# LCMeter_test_power_inverter_VER2.net
KiCad netlist of a schematic drawn in EAGLE
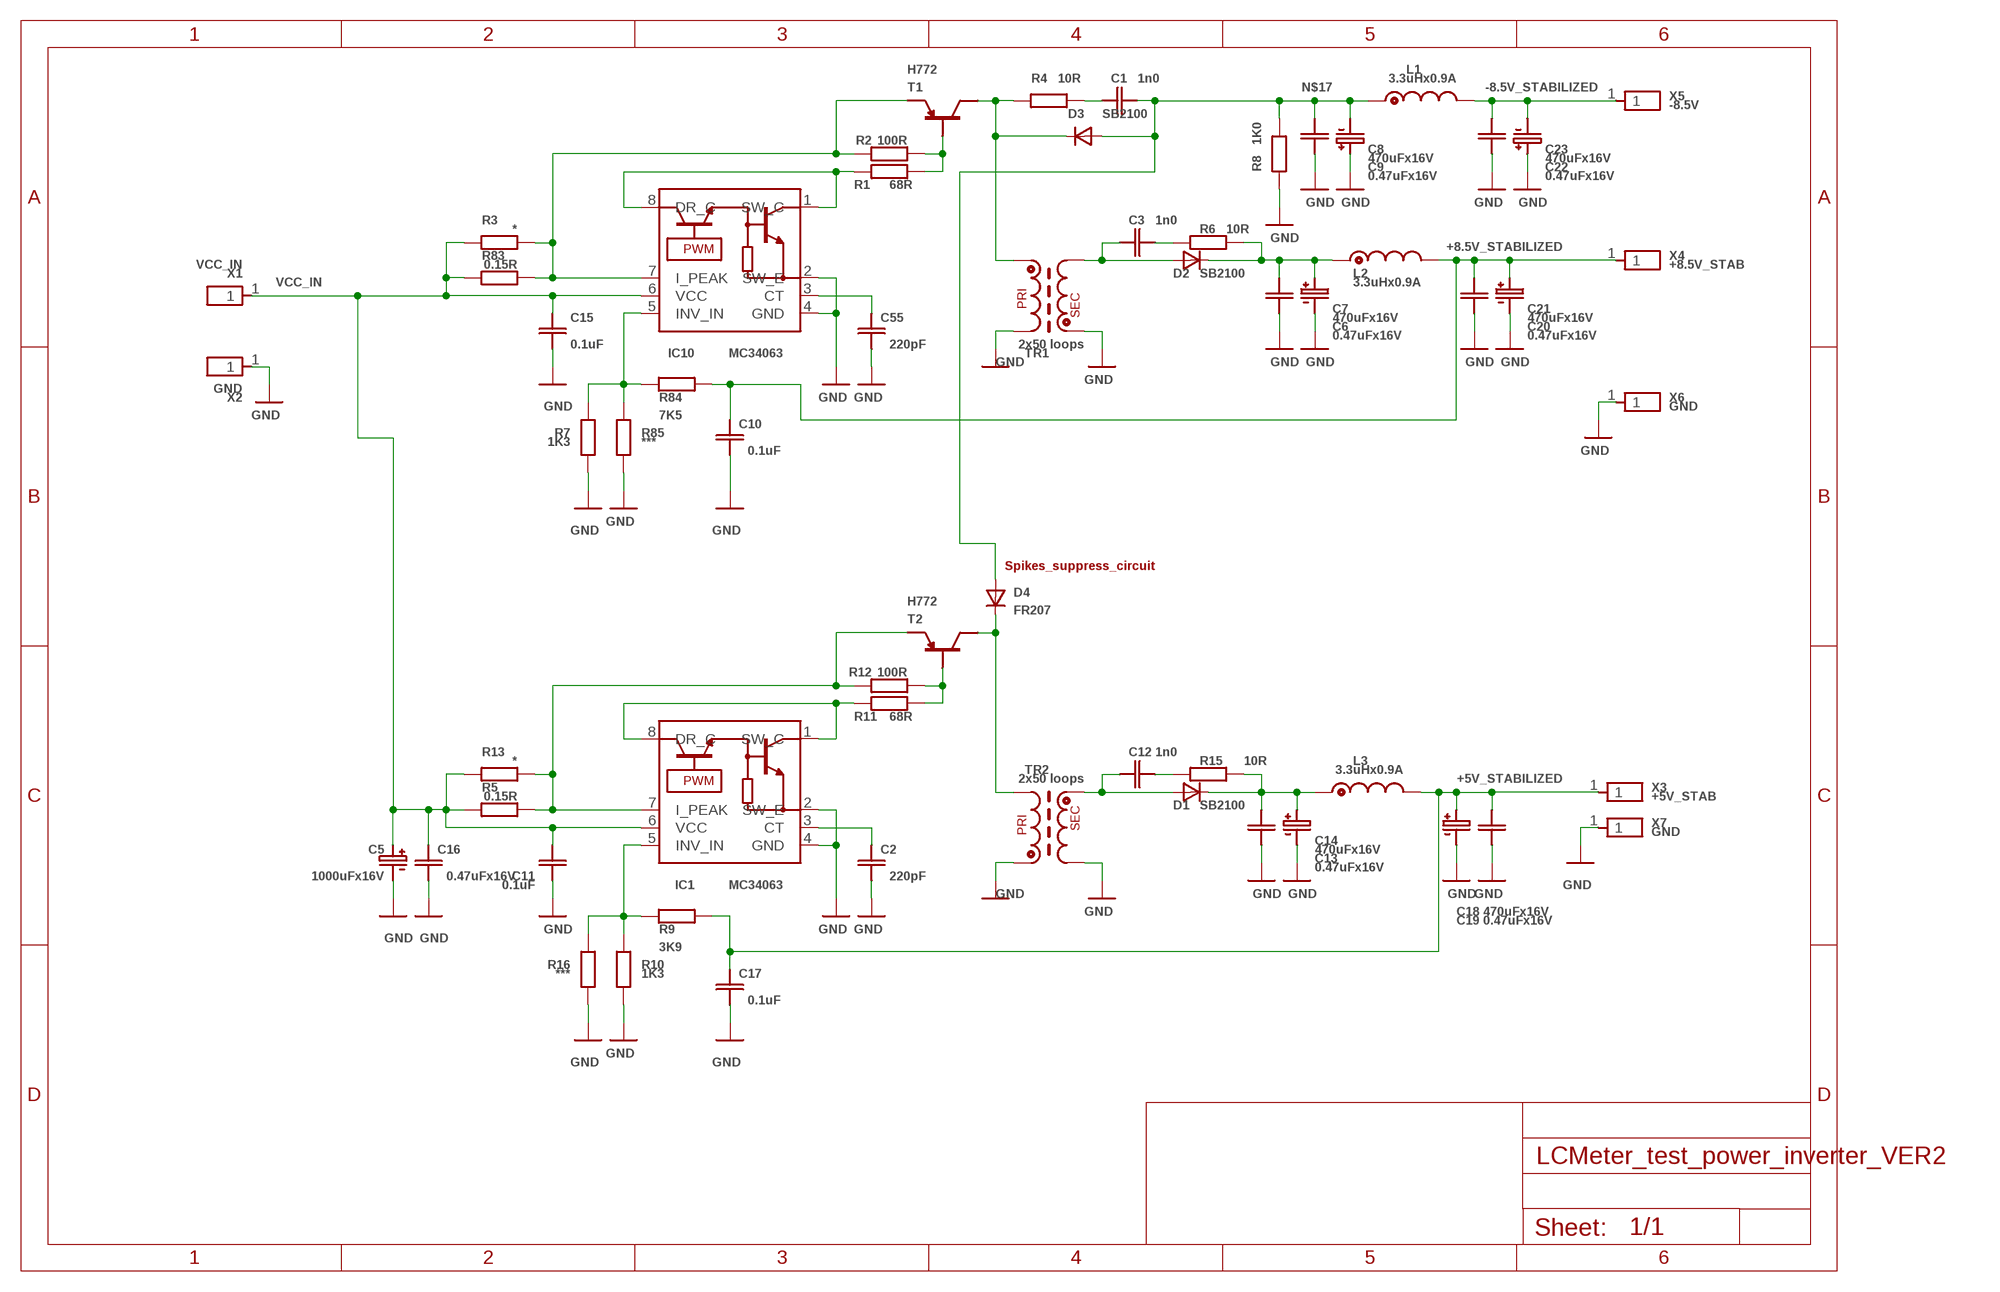
[diagram p0: schematic, sheet 1]

(export (version "E")
  (design (tool "Eeschema 10.0.6"))
  (components
    (comp (ref "C1")
      (value "1n0")
      (footprint "eagle-import:RSMD_0805")
      (libsource (lib "eagle-import") (part "CSMD_0805"))
    )
    (comp (ref "C2")
      (value "220pF")
      (footprint "eagle-import:RSMD_0805")
      (libsource (lib "eagle-import") (part "CSMD_0805"))
    )
    (comp (ref "C3")
      (value "1n0")
      (footprint "eagle-import:RSMD_0805")
      (libsource (lib "eagle-import") (part "CSMD_0805"))
    )
    (comp (ref "C5")
      (value "1000uFx16V")
      (footprint "eagle-import:CE_10MM")
      (libsource (lib "eagle-import") (part "CE10MM"))
    )
    (comp (ref "C6")
      (value "0.47uFx16V")
      (footprint "eagle-import:RSMD_1206_BIG_GAP")
      (libsource (lib "eagle-import") (part "CSMD_1206_BIG_GAP"))
    )
    (comp (ref "C7")
      (value "470uFx16V")
      (footprint "eagle-import:CE_10MM")
      (libsource (lib "eagle-import") (part "CE10MM"))
    )
    (comp (ref "C8")
      (value "470uFx16V")
      (footprint "eagle-import:CE_10MM")
      (libsource (lib "eagle-import") (part "CE10MM"))
    )
    (comp (ref "C9")
      (value "0.47uFx16V")
      (footprint "eagle-import:RSMD_1206_BIG_GAP")
      (libsource (lib "eagle-import") (part "CSMD_1206_BIG_GAP"))
    )
    (comp (ref "C10")
      (value "0.1uF")
      (footprint "eagle-import:RSMD_0805")
      (libsource (lib "eagle-import") (part "CSMD_0805"))
    )
    (comp (ref "C11")
      (value "0.1uF")
      (footprint "eagle-import:RSMD_0805")
      (libsource (lib "eagle-import") (part "CSMD_0805"))
    )
    (comp (ref "C12")
      (value "1n0")
      (footprint "eagle-import:RSMD_0805")
      (libsource (lib "eagle-import") (part "CSMD_0805"))
    )
    (comp (ref "C13")
      (value "0.47uFx16V")
      (footprint "eagle-import:RSMD_1206_BIG_GAP")
      (libsource (lib "eagle-import") (part "CSMD_1206_BIG_GAP"))
    )
    (comp (ref "C14")
      (value "470uFx16V")
      (footprint "eagle-import:CE_10MM")
      (libsource (lib "eagle-import") (part "CE10MM"))
    )
    (comp (ref "C15")
      (value "0.1uF")
      (footprint "eagle-import:RSMD_0805")
      (libsource (lib "eagle-import") (part "CSMD_0805"))
    )
    (comp (ref "C16")
      (value "0.47uFx16V")
      (footprint "eagle-import:RSMD_1206")
      (libsource (lib "eagle-import") (part "CSMD_1206"))
    )
    (comp (ref "C17")
      (value "0.1uF")
      (footprint "eagle-import:RSMD_0805")
      (libsource (lib "eagle-import") (part "CSMD_0805"))
    )
    (comp (ref "C18")
      (value "470uFx16V")
      (footprint "eagle-import:CE_10MM")
      (libsource (lib "eagle-import") (part "CE10MM"))
    )
    (comp (ref "C19")
      (value "0.47uFx16V")
      (footprint "eagle-import:RSMD_1206_BIG_GAP")
      (libsource (lib "eagle-import") (part "CSMD_1206_BIG_GAP"))
    )
    (comp (ref "C20")
      (value "0.47uFx16V")
      (footprint "eagle-import:RSMD_1206_BIG_GAP")
      (libsource (lib "eagle-import") (part "CSMD_1206_BIG_GAP"))
    )
    (comp (ref "C21")
      (value "470uFx16V")
      (footprint "eagle-import:CE_10MM")
      (libsource (lib "eagle-import") (part "CE10MM"))
    )
    (comp (ref "C22")
      (value "0.47uFx16V")
      (footprint "eagle-import:RSMD_1206_BIG_GAP")
      (libsource (lib "eagle-import") (part "CSMD_1206_BIG_GAP"))
    )
    (comp (ref "C23")
      (value "470uFx16V")
      (footprint "eagle-import:CE_10MM")
      (libsource (lib "eagle-import") (part "CE10MM"))
    )
    (comp (ref "C55")
      (value "220pF")
      (footprint "eagle-import:RSMD_0805")
      (libsource (lib "eagle-import") (part "CSMD_0805"))
    )
    (comp (ref "D1")
      (value "SB2100")
      (footprint "eagle-import:DO-41_5MM")
      (libsource (lib "eagle-import") (part "1N4001DO-41_5MM"))
    )
    (comp (ref "D2")
      (value "SB2100")
      (footprint "eagle-import:DO-41_5MM")
      (libsource (lib "eagle-import") (part "1N4001DO-41_5MM"))
    )
    (comp (ref "D3")
      (value "SB2100")
      (footprint "eagle-import:DO-41_5MM")
      (libsource (lib "eagle-import") (part "1N4001DO-41_5MM"))
    )
    (comp (ref "D4")
      (value "FR207")
      (footprint "eagle-import:DO-41_20MM")
      (libsource (lib "eagle-import") (part "1N4001DO-41_20MM"))
    )
    (comp (ref "IC1")
      (value "MC34063")
      (footprint "eagle-import:DIP8")
      (libsource (lib "eagle-import") (part "MC34063(DIP8)"))
    )
    (comp (ref "IC10")
      (value "MC34063")
      (footprint "eagle-import:DIP8")
      (libsource (lib "eagle-import") (part "MC34063(DIP8)"))
    )
    (comp (ref "L1")
      (value "3.3uHx0.9A")
      (footprint "eagle-import:L_SENIA")
      (libsource (lib "eagle-import") (part "L(SENIA)"))
    )
    (comp (ref "L2")
      (value "3.3uHx0.9A")
      (footprint "eagle-import:L_SENIA")
      (libsource (lib "eagle-import") (part "L(SENIA)"))
    )
    (comp (ref "L3")
      (value "3.3uHx0.9A")
      (footprint "eagle-import:L_SENIA")
      (libsource (lib "eagle-import") (part "L(SENIA)"))
    )
    (comp (ref "R1")
      (value "68R")
      (footprint "eagle-import:RSMD_0805")
      (libsource (lib "eagle-import") (part "RSMD_0805"))
    )
    (comp (ref "R2")
      (value "100R")
      (footprint "eagle-import:RSMD_0805")
      (libsource (lib "eagle-import") (part "RSMD_0805"))
    )
    (comp (ref "R3")
      (value "*")
      (footprint "eagle-import:RSMD_1206_BIG_GAP")
      (libsource (lib "eagle-import") (part "RSMD_1206_BIG_GAP"))
    )
    (comp (ref "R4")
      (value "10R")
      (footprint "eagle-import:RSMD_0805")
      (libsource (lib "eagle-import") (part "RSMD_0805"))
    )
    (comp (ref "R5")
      (value "0.15R")
      (footprint "eagle-import:RSMD_1206_BIG_GAP")
      (libsource (lib "eagle-import") (part "RSMD_1206_BIG_GAP"))
    )
    (comp (ref "R6")
      (value "10R")
      (footprint "eagle-import:RSMD_0805")
      (libsource (lib "eagle-import") (part "RSMD_0805"))
    )
    (comp (ref "R7")
      (value "1K3")
      (footprint "eagle-import:RSMD_0805")
      (libsource (lib "eagle-import") (part "RSMD_0805"))
    )
    (comp (ref "R8")
      (value "1K0")
      (footprint "eagle-import:RSMD_1206_BIG_GAP")
      (libsource (lib "eagle-import") (part "RSMD_1206_BIG_GAP"))
    )
    (comp (ref "R9")
      (value "3K9")
      (footprint "eagle-import:RSMD_0805")
      (libsource (lib "eagle-import") (part "RSMD_0805"))
    )
    (comp (ref "R10")
      (value "1K3")
      (footprint "eagle-import:RSMD_0805")
      (libsource (lib "eagle-import") (part "RSMD_0805"))
    )
    (comp (ref "R11")
      (value "68R")
      (footprint "eagle-import:RSMD_0805")
      (libsource (lib "eagle-import") (part "RSMD_0805"))
    )
    (comp (ref "R12")
      (value "100R")
      (footprint "eagle-import:RSMD_0805")
      (libsource (lib "eagle-import") (part "RSMD_0805"))
    )
    (comp (ref "R13")
      (value "*")
      (footprint "eagle-import:RSMD_1206_BIG_GAP")
      (libsource (lib "eagle-import") (part "RSMD_1206_BIG_GAP"))
    )
    (comp (ref "R15")
      (value "10R")
      (footprint "eagle-import:RSMD_0805")
      (libsource (lib "eagle-import") (part "RSMD_0805"))
    )
    (comp (ref "R16")
      (value "***")
      (footprint "eagle-import:RSMD_0805")
      (libsource (lib "eagle-import") (part "RSMD_0805"))
    )
    (comp (ref "R83")
      (value "0.15R")
      (footprint "eagle-import:RSMD_1206_BIG_GAP")
      (libsource (lib "eagle-import") (part "RSMD_1206_BIG_GAP"))
    )
    (comp (ref "R84")
      (value "7K5")
      (footprint "eagle-import:RSMD_0805")
      (libsource (lib "eagle-import") (part "RSMD_0805"))
    )
    (comp (ref "R85")
      (value "***")
      (footprint "eagle-import:RSMD_0805")
      (libsource (lib "eagle-import") (part "RSMD_0805"))
    )
    (comp (ref "T1")
      (value "H772")
      (footprint "eagle-import:DPAK")
      (libsource (lib "eagle-import") (part "H772_PNPDPAK"))
    )
    (comp (ref "T2")
      (value "H772")
      (footprint "eagle-import:DPAK")
      (libsource (lib "eagle-import") (part "H772_PNPDPAK"))
    )
    (comp (ref "TR1")
      (value "2x50 loops")
      (footprint "eagle-import:RING_16X8_2WIND")
      (libsource (lib "eagle-import") (part "TRANS_2WIND(RING_16X8)"))
    )
    (comp (ref "TR2")
      (value "2x50 loops")
      (footprint "eagle-import:RING_16X8_2WIND")
      (libsource (lib "eagle-import") (part "TRANS_2WIND(RING_16X8)"))
    )
    (comp (ref "X1")
      (value "VCC_IN")
      (footprint "eagle-import:PIN1X1_3.5MM_PWR")
      (libsource (lib "eagle-import") (part "PIN1X13.5MM_PWR"))
    )
    (comp (ref "X2")
      (value "GND")
      (footprint "eagle-import:PIN1X1_3.5MM_PWR")
      (libsource (lib "eagle-import") (part "PIN1X13.5MM_PWR"))
    )
    (comp (ref "X3")
      (value "+5V_STAB")
      (footprint "eagle-import:PIN1X1_3.5MM_PWR")
      (libsource (lib "eagle-import") (part "PIN1X13.5MM_PWR"))
    )
    (comp (ref "X4")
      (value "+8.5V_STAB")
      (footprint "eagle-import:PIN1X1_3.5MM_PWR")
      (libsource (lib "eagle-import") (part "PIN1X13.5MM_PWR"))
    )
    (comp (ref "X5")
      (value "-8.5V")
      (footprint "eagle-import:PIN1X1_3.5MM_PWR")
      (libsource (lib "eagle-import") (part "PIN1X13.5MM_PWR"))
    )
    (comp (ref "X6")
      (value "GND")
      (footprint "eagle-import:PIN1X1_3.5MM_PWR")
      (libsource (lib "eagle-import") (part "PIN1X13.5MM_PWR"))
    )
    (comp (ref "X7")
      (value "GND")
      (footprint "eagle-import:PIN1X1_3.5MM_PWR")
      (libsource (lib "eagle-import") (part "PIN1X13.5MM_PWR"))
    )
  )
  (nets
    (net (code "1") (name "/+5V_STABILIZED") (class "Default")
      (node (ref "C17") (pin "PAD_1") (pinfunction "PIN1_PAD_1") (pintype "bidirectional"))
      (node (ref "C18") (pin "PLUS") (pinfunction "PLUS_PLUS") (pintype "bidirectional"))
      (node (ref "C19") (pin "PAD_1") (pinfunction "PIN1_PAD_1") (pintype "bidirectional"))
      (node (ref "L3") (pin "1") (pinfunction "END_1") (pintype "bidirectional"))
      (node (ref "R9") (pin "PAD_1") (pinfunction "PIN1_PAD_1") (pintype "passive"))
      (node (ref "X3") (pin "1") (pinfunction "1_1") (pintype "bidirectional"))
    )
    (net (code "2") (name "/+8.5V_STABILIZED") (class "Default")
      (node (ref "C10") (pin "PAD_1") (pinfunction "PIN1_PAD_1") (pintype "bidirectional"))
      (node (ref "C20") (pin "PAD_1") (pinfunction "PIN1_PAD_1") (pintype "bidirectional"))
      (node (ref "C21") (pin "PLUS") (pinfunction "PLUS_PLUS") (pintype "bidirectional"))
      (node (ref "L2") (pin "1") (pinfunction "END_1") (pintype "bidirectional"))
      (node (ref "R84") (pin "PAD_1") (pinfunction "PIN1_PAD_1") (pintype "passive"))
      (node (ref "X4") (pin "1") (pinfunction "1_1") (pintype "bidirectional"))
    )
    (net (code "3") (name "/-8.5V_STABILIZED") (class "Default")
      (node (ref "C22") (pin "PAD_1") (pinfunction "PIN1_PAD_1") (pintype "bidirectional"))
      (node (ref "C23") (pin "MINUS") (pinfunction "MINUS_MINUS") (pintype "bidirectional"))
      (node (ref "L1") (pin "1") (pinfunction "END_1") (pintype "bidirectional"))
      (node (ref "X5") (pin "1") (pinfunction "1_1") (pintype "bidirectional"))
    )
    (net (code "4") (name "/N$17") (class "Default")
      (node (ref "C1") (pin "PAD_0") (pinfunction "PIN0_PAD_0") (pintype "bidirectional"))
      (node (ref "C8") (pin "MINUS") (pinfunction "MINUS_MINUS") (pintype "bidirectional"))
      (node (ref "C9") (pin "PAD_1") (pinfunction "PIN1_PAD_1") (pintype "bidirectional"))
      (node (ref "D3") (pin "ANODE") (pinfunction "ANODE_ANODE") (pintype "passive"))
      (node (ref "D4") (pin "ANODE") (pinfunction "ANODE_ANODE") (pintype "passive"))
      (node (ref "L1") (pin "2") (pinfunction "START_2") (pintype "bidirectional"))
      (node (ref "R8") (pin "PAD_0") (pinfunction "PIN0_PAD_0") (pintype "passive"))
    )
    (net (code "5") (name "/VCC_IN") (class "Default")
      (node (ref "C11") (pin "PAD_1") (pinfunction "PIN1_PAD_1") (pintype "bidirectional"))
      (node (ref "C15") (pin "PAD_1") (pinfunction "PIN1_PAD_1") (pintype "bidirectional"))
      (node (ref "C16") (pin "PAD_1") (pinfunction "PIN1_PAD_1") (pintype "bidirectional"))
      (node (ref "C5") (pin "PLUS") (pinfunction "PLUS_PLUS") (pintype "bidirectional"))
      (node (ref "IC1") (pin "6") (pinfunction "VCC_6") (pintype "bidirectional"))
      (node (ref "IC10") (pin "6") (pinfunction "VCC_6") (pintype "bidirectional"))
      (node (ref "R13") (pin "PAD_0") (pinfunction "PIN0_PAD_0") (pintype "passive"))
      (node (ref "R3") (pin "PAD_0") (pinfunction "PIN0_PAD_0") (pintype "passive"))
      (node (ref "R5") (pin "PAD_0") (pinfunction "PIN0_PAD_0") (pintype "passive"))
      (node (ref "R83") (pin "PAD_0") (pinfunction "PIN0_PAD_0") (pintype "passive"))
      (node (ref "X1") (pin "1") (pinfunction "1_1") (pintype "bidirectional"))
    )
    (net (code "6") (name "GND") (class "Default")
      (node (ref "C10") (pin "PAD_0") (pinfunction "PIN0_PAD_0") (pintype "bidirectional"))
      (node (ref "C11") (pin "PAD_0") (pinfunction "PIN0_PAD_0") (pintype "bidirectional"))
      (node (ref "C13") (pin "PAD_0") (pinfunction "PIN0_PAD_0") (pintype "bidirectional"))
      (node (ref "C14") (pin "MINUS") (pinfunction "MINUS_MINUS") (pintype "bidirectional"))
      (node (ref "C15") (pin "PAD_0") (pinfunction "PIN0_PAD_0") (pintype "bidirectional"))
      (node (ref "C16") (pin "PAD_0") (pinfunction "PIN0_PAD_0") (pintype "bidirectional"))
      (node (ref "C17") (pin "PAD_0") (pinfunction "PIN0_PAD_0") (pintype "bidirectional"))
      (node (ref "C18") (pin "MINUS") (pinfunction "MINUS_MINUS") (pintype "bidirectional"))
      (node (ref "C19") (pin "PAD_0") (pinfunction "PIN0_PAD_0") (pintype "bidirectional"))
      (node (ref "C2") (pin "PAD_0") (pinfunction "PIN0_PAD_0") (pintype "bidirectional"))
      (node (ref "C20") (pin "PAD_0") (pinfunction "PIN0_PAD_0") (pintype "bidirectional"))
      (node (ref "C21") (pin "MINUS") (pinfunction "MINUS_MINUS") (pintype "bidirectional"))
      (node (ref "C22") (pin "PAD_0") (pinfunction "PIN0_PAD_0") (pintype "bidirectional"))
      (node (ref "C23") (pin "PLUS") (pinfunction "PLUS_PLUS") (pintype "bidirectional"))
      (node (ref "C5") (pin "MINUS") (pinfunction "MINUS_MINUS") (pintype "bidirectional"))
      (node (ref "C55") (pin "PAD_0") (pinfunction "PIN0_PAD_0") (pintype "bidirectional"))
      (node (ref "C6") (pin "PAD_0") (pinfunction "PIN0_PAD_0") (pintype "bidirectional"))
      (node (ref "C7") (pin "MINUS") (pinfunction "MINUS_MINUS") (pintype "bidirectional"))
      (node (ref "C8") (pin "PLUS") (pinfunction "PLUS_PLUS") (pintype "bidirectional"))
      (node (ref "C9") (pin "PAD_0") (pinfunction "PIN0_PAD_0") (pintype "bidirectional"))
      (node (ref "IC1") (pin "2") (pinfunction "SW_E_2") (pintype "bidirectional"))
      (node (ref "IC1") (pin "4") (pinfunction "GND_4") (pintype "bidirectional"))
      (node (ref "IC10") (pin "2") (pinfunction "SW_E_2") (pintype "bidirectional"))
      (node (ref "IC10") (pin "4") (pinfunction "GND_4") (pintype "bidirectional"))
      (node (ref "R10") (pin "PAD_0") (pinfunction "PIN0_PAD_0") (pintype "passive"))
      (node (ref "R16") (pin "PAD_0") (pinfunction "PIN0_PAD_0") (pintype "passive"))
      (node (ref "R7") (pin "PAD_0") (pinfunction "PIN0_PAD_0") (pintype "passive"))
      (node (ref "R8") (pin "PAD_1") (pinfunction "PIN1_PAD_1") (pintype "passive"))
      (node (ref "R85") (pin "PAD_0") (pinfunction "PIN0_PAD_0") (pintype "passive"))
      (node (ref "TR1") (pin "W1_END") (pinfunction "PRI_END_W1_END") (pintype "bidirectional"))
      (node (ref "TR1") (pin "W2_START") (pinfunction "SEC_START_W2_START") (pintype "bidirectional"))
      (node (ref "TR2") (pin "W1_START") (pinfunction "PRI_START_W1_START") (pintype "bidirectional"))
      (node (ref "TR2") (pin "W2_END") (pinfunction "SEC_END_W2_END") (pintype "bidirectional"))
      (node (ref "X2") (pin "1") (pinfunction "1_1") (pintype "bidirectional"))
      (node (ref "X6") (pin "1") (pinfunction "1_1") (pintype "bidirectional"))
      (node (ref "X7") (pin "1") (pinfunction "1_1") (pintype "bidirectional"))
    )
    (net (code "7") (name "Net-(C1-PIN1)") (class "Default")
      (node (ref "C1") (pin "PAD_1") (pinfunction "PIN1_PAD_1") (pintype "bidirectional"))
      (node (ref "R4") (pin "PAD_0") (pinfunction "PIN0_PAD_0") (pintype "passive"))
    )
    (net (code "8") (name "Net-(C2-PIN1)") (class "Default")
      (node (ref "C2") (pin "PAD_1") (pinfunction "PIN1_PAD_1") (pintype "bidirectional"))
      (node (ref "IC1") (pin "3") (pinfunction "CT_3") (pintype "bidirectional"))
    )
    (net (code "9") (name "Net-(C3-PIN0)") (class "Default")
      (node (ref "C3") (pin "PAD_0") (pinfunction "PIN0_PAD_0") (pintype "bidirectional"))
      (node (ref "R6") (pin "PAD_1") (pinfunction "PIN1_PAD_1") (pintype "passive"))
    )
    (net (code "10") (name "Net-(C3-PIN1)") (class "Default")
      (node (ref "C3") (pin "PAD_1") (pinfunction "PIN1_PAD_1") (pintype "bidirectional"))
      (node (ref "D2") (pin "ANODE") (pinfunction "ANODE_ANODE") (pintype "passive"))
      (node (ref "TR1") (pin "W2_END") (pinfunction "SEC_END_W2_END") (pintype "bidirectional"))
    )
    (net (code "11") (name "Net-(C6-PIN1)") (class "Default")
      (node (ref "C6") (pin "PAD_1") (pinfunction "PIN1_PAD_1") (pintype "bidirectional"))
      (node (ref "C7") (pin "PLUS") (pinfunction "PLUS_PLUS") (pintype "bidirectional"))
      (node (ref "D2") (pin "CATHODE") (pinfunction "CATHODE_CATHODE") (pintype "passive"))
      (node (ref "L2") (pin "2") (pinfunction "START_2") (pintype "bidirectional"))
      (node (ref "R6") (pin "PAD_0") (pinfunction "PIN0_PAD_0") (pintype "passive"))
    )
    (net (code "12") (name "Net-(C12-PIN0)") (class "Default")
      (node (ref "C12") (pin "PAD_0") (pinfunction "PIN0_PAD_0") (pintype "bidirectional"))
      (node (ref "R15") (pin "PAD_1") (pinfunction "PIN1_PAD_1") (pintype "passive"))
    )
    (net (code "13") (name "Net-(C12-PIN1)") (class "Default")
      (node (ref "C12") (pin "PAD_1") (pinfunction "PIN1_PAD_1") (pintype "bidirectional"))
      (node (ref "D1") (pin "ANODE") (pinfunction "ANODE_ANODE") (pintype "passive"))
      (node (ref "TR2") (pin "W2_START") (pinfunction "SEC_START_W2_START") (pintype "bidirectional"))
    )
    (net (code "14") (name "Net-(C13-PIN1)") (class "Default")
      (node (ref "C13") (pin "PAD_1") (pinfunction "PIN1_PAD_1") (pintype "bidirectional"))
      (node (ref "C14") (pin "PLUS") (pinfunction "PLUS_PLUS") (pintype "bidirectional"))
      (node (ref "D1") (pin "CATHODE") (pinfunction "CATHODE_CATHODE") (pintype "passive"))
      (node (ref "L3") (pin "2") (pinfunction "START_2") (pintype "bidirectional"))
      (node (ref "R15") (pin "PAD_0") (pinfunction "PIN0_PAD_0") (pintype "passive"))
    )
    (net (code "15") (name "Net-(C55-PIN1)") (class "Default")
      (node (ref "C55") (pin "PAD_1") (pinfunction "PIN1_PAD_1") (pintype "bidirectional"))
      (node (ref "IC10") (pin "3") (pinfunction "CT_3") (pintype "bidirectional"))
    )
    (net (code "16") (name "Net-(IC1-DR_C)") (class "Default")
      (node (ref "IC1") (pin "1") (pinfunction "SW_C_1") (pintype "bidirectional"))
      (node (ref "IC1") (pin "8") (pinfunction "DR_C_8") (pintype "bidirectional"))
      (node (ref "R11") (pin "PAD_0") (pinfunction "PIN0_PAD_0") (pintype "passive"))
    )
    (net (code "17") (name "Net-(IC1-INV_IN)") (class "Default")
      (node (ref "IC1") (pin "5") (pinfunction "INV_IN_5") (pintype "bidirectional"))
      (node (ref "R10") (pin "PAD_1") (pinfunction "PIN1_PAD_1") (pintype "passive"))
      (node (ref "R16") (pin "PAD_1") (pinfunction "PIN1_PAD_1") (pintype "passive"))
      (node (ref "R9") (pin "PAD_0") (pinfunction "PIN0_PAD_0") (pintype "passive"))
    )
    (net (code "18") (name "Net-(IC1-I_PEAK)") (class "Default")
      (node (ref "IC1") (pin "7") (pinfunction "I_PEAK_7") (pintype "bidirectional"))
      (node (ref "R12") (pin "PAD_1") (pinfunction "PIN1_PAD_1") (pintype "passive"))
      (node (ref "R13") (pin "PAD_1") (pinfunction "PIN1_PAD_1") (pintype "passive"))
      (node (ref "R5") (pin "PAD_1") (pinfunction "PIN1_PAD_1") (pintype "passive"))
      (node (ref "T2") (pin "3") (pinfunction "E_3") (pintype "bidirectional"))
    )
    (net (code "19") (name "Net-(IC10-DR_C)") (class "Default")
      (node (ref "IC10") (pin "1") (pinfunction "SW_C_1") (pintype "bidirectional"))
      (node (ref "IC10") (pin "8") (pinfunction "DR_C_8") (pintype "bidirectional"))
      (node (ref "R1") (pin "PAD_0") (pinfunction "PIN0_PAD_0") (pintype "passive"))
    )
    (net (code "20") (name "Net-(IC10-INV_IN)") (class "Default")
      (node (ref "IC10") (pin "5") (pinfunction "INV_IN_5") (pintype "bidirectional"))
      (node (ref "R7") (pin "PAD_1") (pinfunction "PIN1_PAD_1") (pintype "passive"))
      (node (ref "R84") (pin "PAD_0") (pinfunction "PIN0_PAD_0") (pintype "passive"))
      (node (ref "R85") (pin "PAD_1") (pinfunction "PIN1_PAD_1") (pintype "passive"))
    )
    (net (code "21") (name "Net-(IC10-I_PEAK)") (class "Default")
      (node (ref "IC10") (pin "7") (pinfunction "I_PEAK_7") (pintype "bidirectional"))
      (node (ref "R2") (pin "PAD_1") (pinfunction "PIN1_PAD_1") (pintype "passive"))
      (node (ref "R3") (pin "PAD_1") (pinfunction "PIN1_PAD_1") (pintype "passive"))
      (node (ref "R83") (pin "PAD_1") (pinfunction "PIN1_PAD_1") (pintype "passive"))
      (node (ref "T1") (pin "3") (pinfunction "E_3") (pintype "bidirectional"))
    )
    (net (code "22") (name "Net-(R1-PIN1)") (class "Default")
      (node (ref "R1") (pin "PAD_1") (pinfunction "PIN1_PAD_1") (pintype "passive"))
      (node (ref "R2") (pin "PAD_0") (pinfunction "PIN0_PAD_0") (pintype "passive"))
      (node (ref "T1") (pin "1") (pinfunction "B_1") (pintype "bidirectional"))
    )
    (net (code "23") (name "Net-(R4-PIN1)") (class "Default")
      (node (ref "D3") (pin "CATHODE") (pinfunction "CATHODE_CATHODE") (pintype "passive"))
      (node (ref "R4") (pin "PAD_1") (pinfunction "PIN1_PAD_1") (pintype "passive"))
      (node (ref "T1") (pin "2") (pinfunction "C_2") (pintype "bidirectional"))
      (node (ref "TR1") (pin "W1_START") (pinfunction "PRI_START_W1_START") (pintype "bidirectional"))
    )
    (net (code "24") (name "Net-(R11-PIN1)") (class "Default")
      (node (ref "R11") (pin "PAD_1") (pinfunction "PIN1_PAD_1") (pintype "passive"))
      (node (ref "R12") (pin "PAD_0") (pinfunction "PIN0_PAD_0") (pintype "passive"))
      (node (ref "T2") (pin "1") (pinfunction "B_1") (pintype "bidirectional"))
    )
    (net (code "25") (name "Net-(T2-C)") (class "Default")
      (node (ref "D4") (pin "CATHODE") (pinfunction "CATHODE_CATHODE") (pintype "passive"))
      (node (ref "T2") (pin "2") (pinfunction "C_2") (pintype "bidirectional"))
      (node (ref "TR2") (pin "W1_END") (pinfunction "PRI_END_W1_END") (pintype "bidirectional"))
    )
  )
)
